# ece411-t10-Receiver.net
KiCad netlist of a schematic drawn in EAGLE
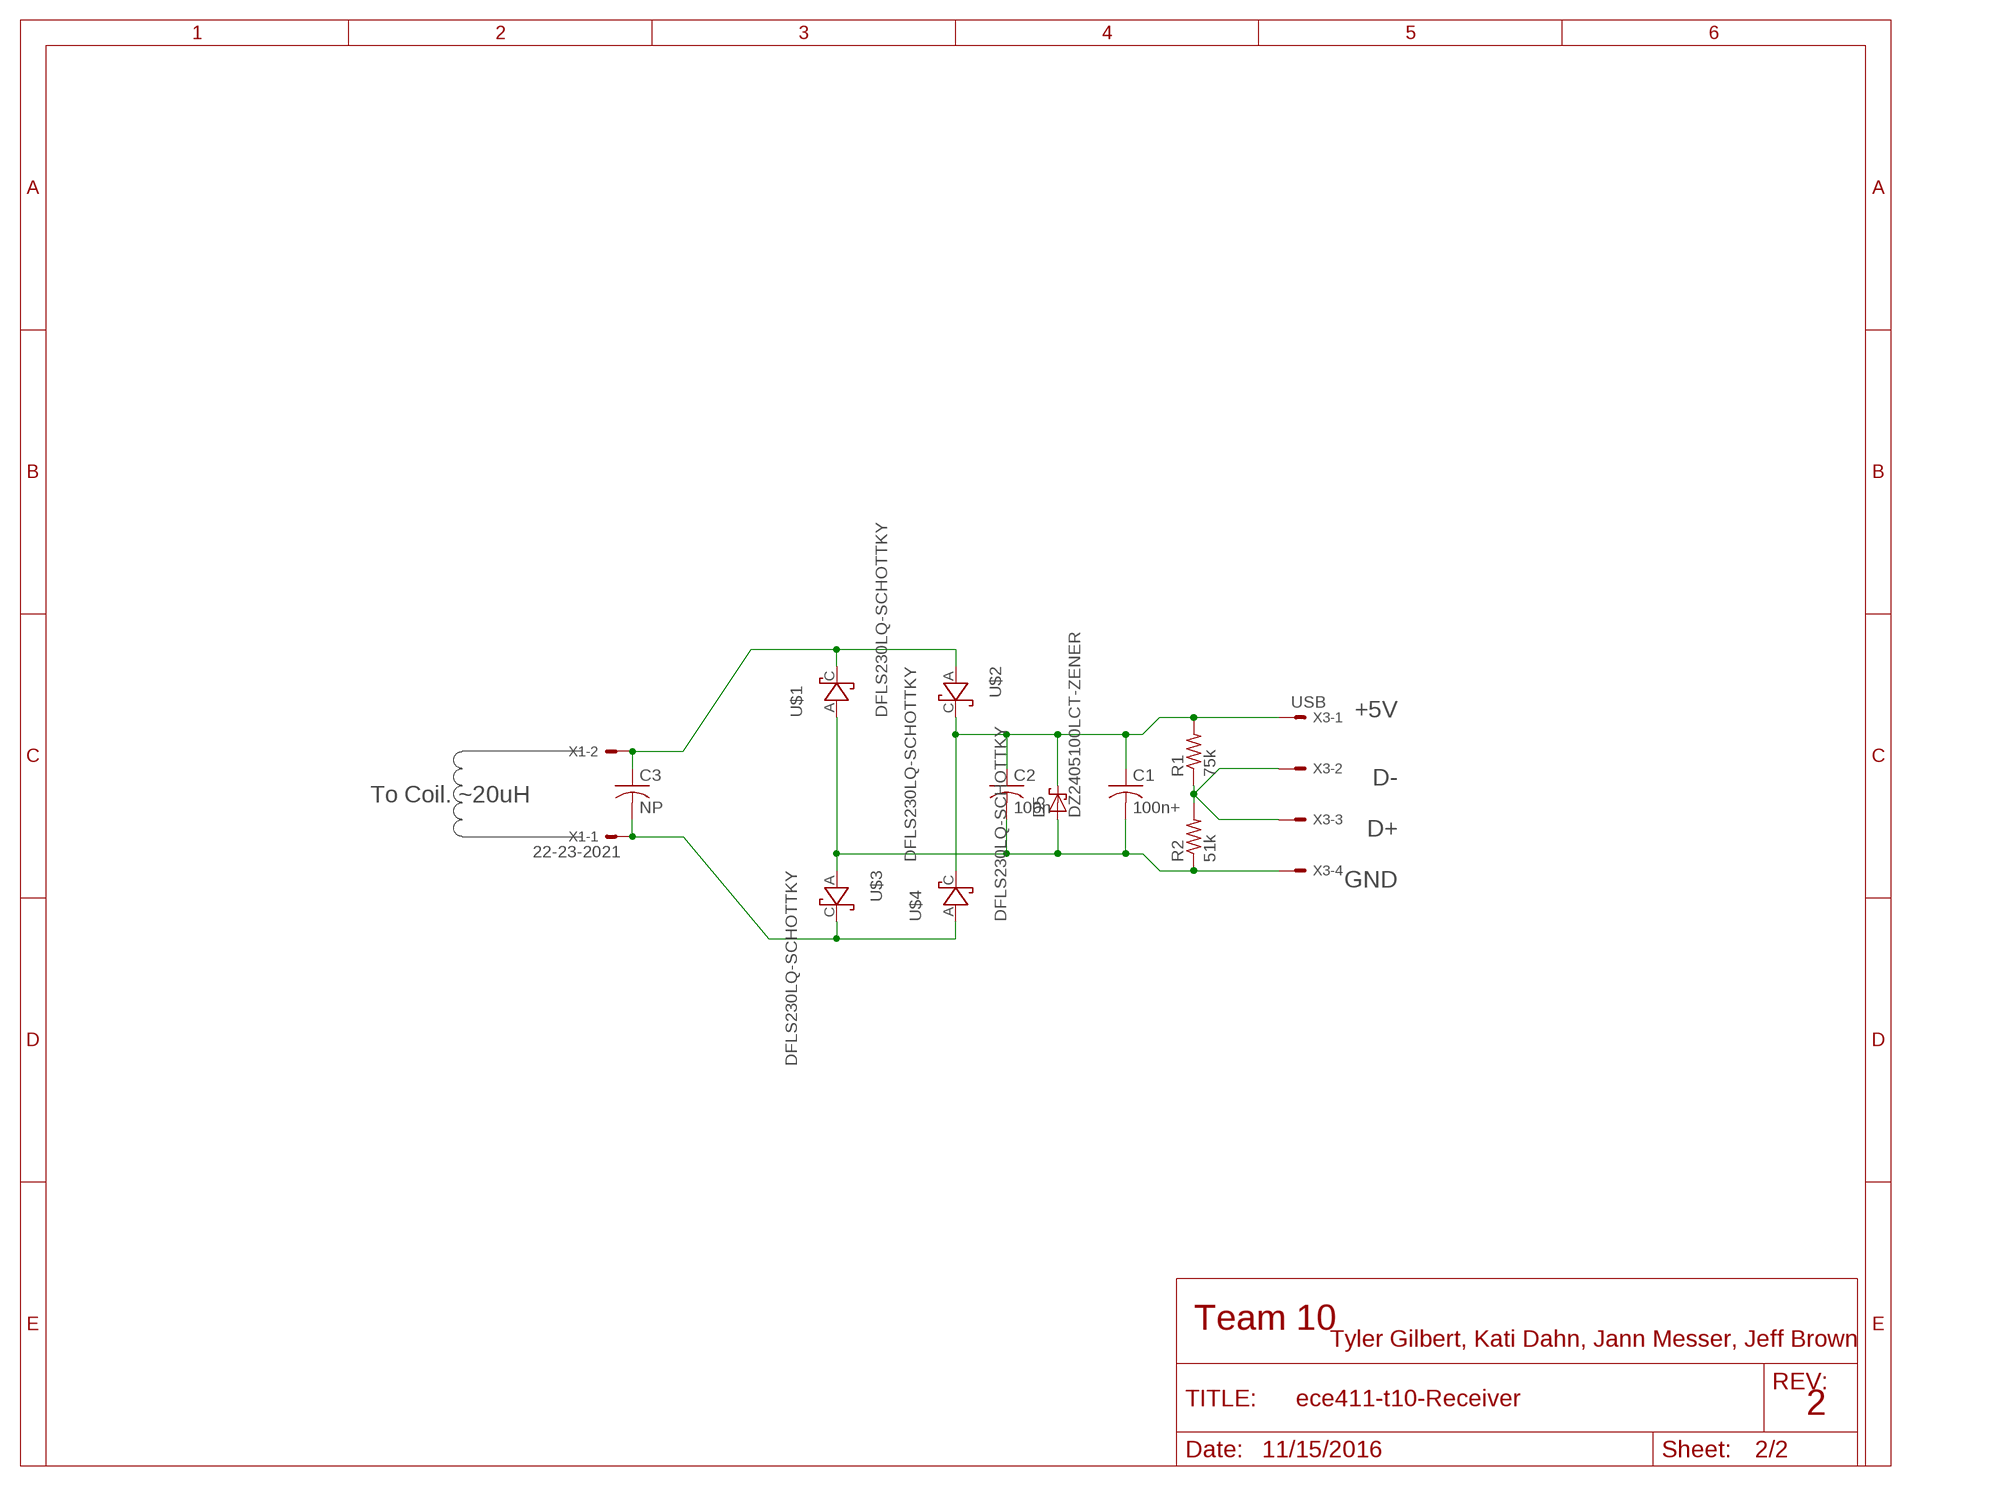
[diagram p0: schematic, sheet 1]

(export (version "E")
  (design (tool "Eeschema 10.0.6"))
  (components
    (comp (ref "C1")
      (value "100n+")
      (footprint "eagle-import:C0805")
      (libsource (lib "eagle-import") (part "C-USC0805"))
    )
    (comp (ref "C2")
      (value "100n")
      (footprint "eagle-import:C0805")
      (libsource (lib "eagle-import") (part "C-USC0805"))
    )
    (comp (ref "C3")
      (value "NP")
      (footprint "eagle-import:C0805")
      (libsource (lib "eagle-import") (part "C-USC0805"))
    )
    (comp (ref "D5")
      (value "DZ2405100LCT-ZENER")
      (footprint "eagle-import:ZENER_PWR_PKG")
      (libsource (lib "eagle-import") (part "DZ2405100LCT-ZENER"))
    )
    (comp (ref "R1")
      (value "75k")
      (footprint "eagle-import:R0805")
      (libsource (lib "eagle-import") (part "R-US_R0805"))
    )
    (comp (ref "R2")
      (value "51k")
      (footprint "eagle-import:R0805")
      (libsource (lib "eagle-import") (part "R-US_R0805"))
    )
    (comp (ref "U$1")
      (value "DFLS230LQ-SCHOTTKY")
      (footprint "eagle-import:PWRDI123")
      (libsource (lib "eagle-import") (part "DFLS230LQ-SCHOTTKY"))
    )
    (comp (ref "U$2")
      (value "DFLS230LQ-SCHOTTKY")
      (footprint "eagle-import:PWRDI123")
      (libsource (lib "eagle-import") (part "DFLS230LQ-SCHOTTKY"))
    )
    (comp (ref "U$3")
      (value "DFLS230LQ-SCHOTTKY")
      (footprint "eagle-import:PWRDI123")
      (libsource (lib "eagle-import") (part "DFLS230LQ-SCHOTTKY"))
    )
    (comp (ref "U$4")
      (value "DFLS230LQ-SCHOTTKY")
      (footprint "eagle-import:PWRDI123")
      (libsource (lib "eagle-import") (part "DFLS230LQ-SCHOTTKY"))
    )
    (comp (ref "X1")
      (value "22-23-2021")
      (footprint "eagle-import:22-23-2021")
      (fields (field (name "MF") "MOLEX"))
      (libsource (lib "eagle-import") (part "22-23-2021"))
    )
    (comp (ref "X3")
      (value "USB")
      (footprint "eagle-import:22-23-2041")
      (fields (field (name "MF") "MOLEX") (field (name "MPN") "22-23-2041"))
      (libsource (lib "eagle-import") (part "22-23-2041"))
    )
  )
  (nets
    (net (code "1") (name "Net-(X1A-S)") (class "Default")
      (node (ref "C3") (pin "2") (pinfunction "2_2") (pintype "passive"))
      (node (ref "U$3") (pin "C") (pinfunction "C_C") (pintype "bidirectional"))
      (node (ref "U$4") (pin "A") (pinfunction "A_A") (pintype "bidirectional"))
      (node (ref "X1") (pin "1") (pinfunction "S_1") (pintype "passive"))
    )
    (net (code "2") (name "Net-(X1B-S)") (class "Default")
      (node (ref "C3") (pin "1") (pinfunction "1_1") (pintype "passive"))
      (node (ref "U$1") (pin "C") (pinfunction "C_C") (pintype "bidirectional"))
      (node (ref "U$2") (pin "A") (pinfunction "A_A") (pintype "bidirectional"))
      (node (ref "X1") (pin "2") (pinfunction "S_2") (pintype "passive"))
    )
    (net (code "3") (name "Net-(X3A-S)") (class "Default")
      (node (ref "C1") (pin "1") (pinfunction "1_1") (pintype "passive"))
      (node (ref "C2") (pin "1") (pinfunction "1_1") (pintype "passive"))
      (node (ref "D5") (pin "C") (pinfunction "C_C") (pintype "passive"))
      (node (ref "R1") (pin "2") (pinfunction "2_2") (pintype "passive"))
      (node (ref "U$2") (pin "C") (pinfunction "C_C") (pintype "bidirectional"))
      (node (ref "U$4") (pin "C") (pinfunction "C_C") (pintype "bidirectional"))
      (node (ref "X3") (pin "1") (pinfunction "S_1") (pintype "passive"))
    )
    (net (code "4") (name "Net-(X3B-S)") (class "Default")
      (node (ref "R1") (pin "1") (pinfunction "1_1") (pintype "passive"))
      (node (ref "R2") (pin "2") (pinfunction "2_2") (pintype "passive"))
      (node (ref "X3") (pin "2") (pinfunction "S_2") (pintype "passive"))
      (node (ref "X3") (pin "3") (pinfunction "S_3") (pintype "passive"))
    )
    (net (code "5") (name "Net-(X3D-S)") (class "Default")
      (node (ref "C1") (pin "2") (pinfunction "2_2") (pintype "passive"))
      (node (ref "C2") (pin "2") (pinfunction "2_2") (pintype "passive"))
      (node (ref "D5") (pin "A") (pinfunction "A_A") (pintype "passive"))
      (node (ref "R2") (pin "1") (pinfunction "1_1") (pintype "passive"))
      (node (ref "U$1") (pin "A") (pinfunction "A_A") (pintype "bidirectional"))
      (node (ref "U$3") (pin "A") (pinfunction "A_A") (pintype "bidirectional"))
      (node (ref "X3") (pin "4") (pinfunction "S_4") (pintype "passive"))
    )
  )
)
